# VME_buffers_data.net
KiCad netlist of a schematic drawn in Altium Designer
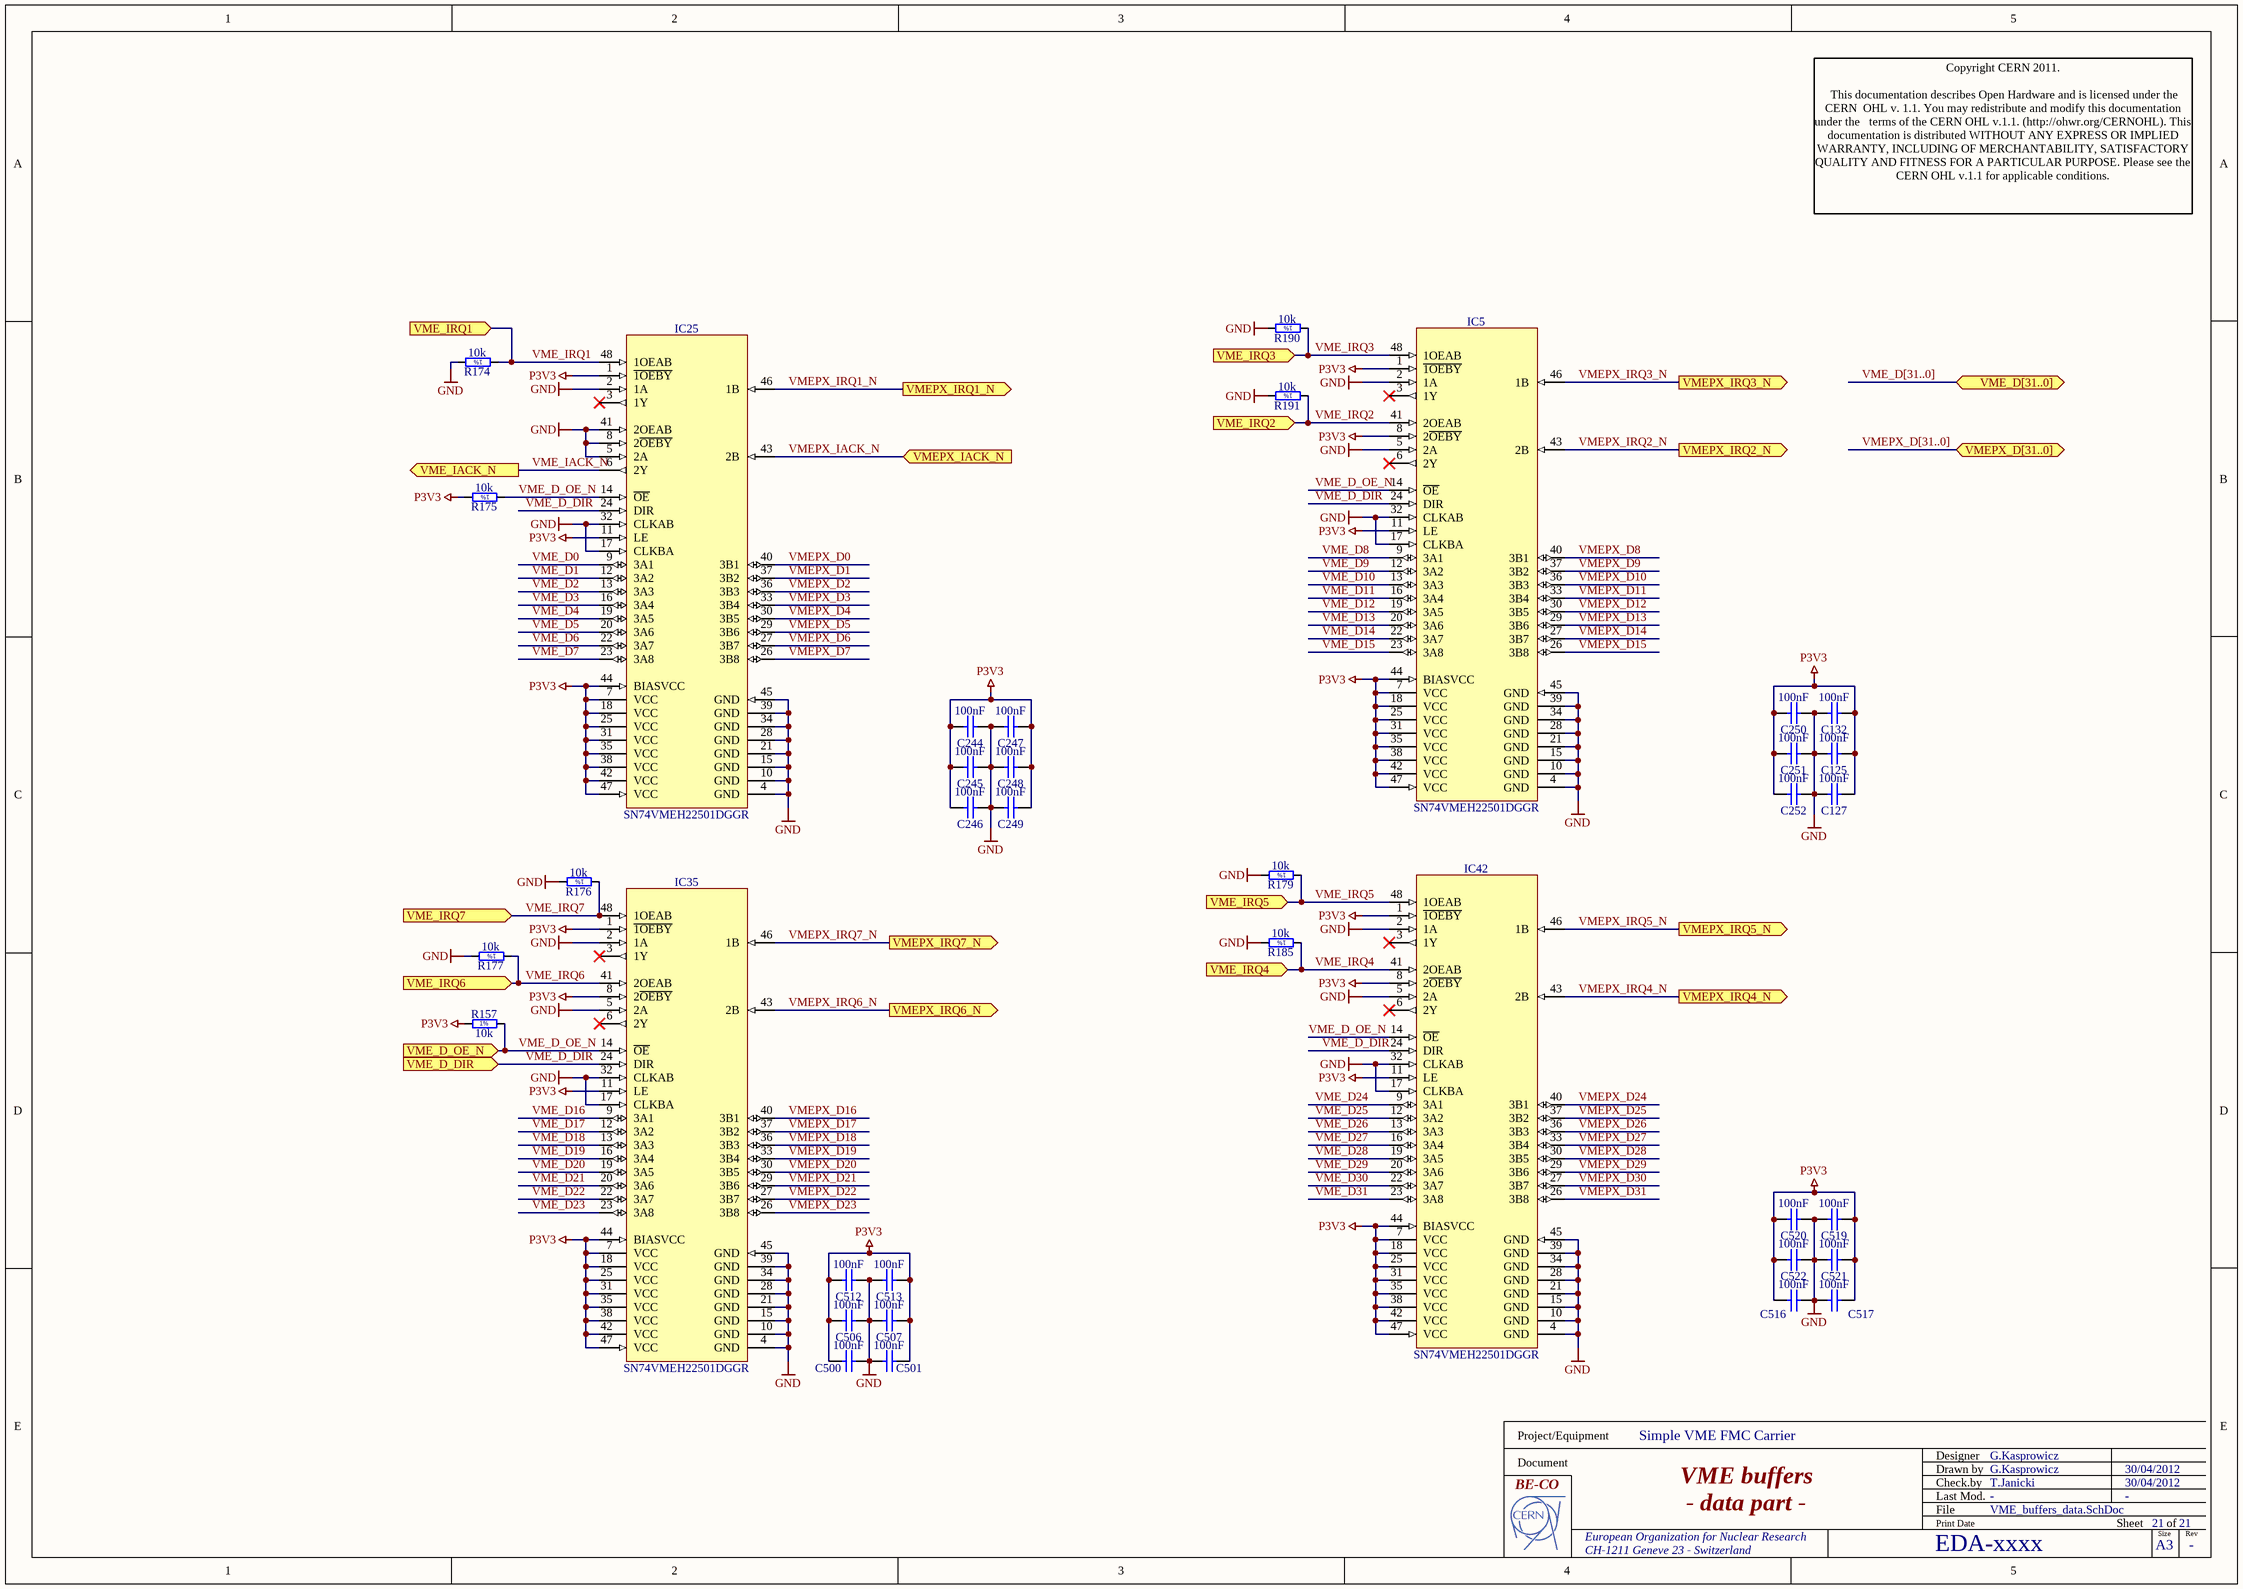
[diagram p0: VME_buffers_data.SchDoc]

(export (version "E")
  (design (tool "Eeschema 10.0.6"))
  (components
    (comp (ref "C125")
      (value "100nF")
      (footprint "CAPC1005X55N")
      (description "Non-polarised capacitor")
      (fields
        (field (name "PART NUMBER") "CC0402_100NF_16V_10%_X7R")
        (field (name "VOLTAGE") "16V")
        (field (name "AUTHOR") "CERN DEM JLC")
      )
      (libsource (lib "Capacitors") (part "Capacitor - non polarized"))
    )
    (comp (ref "C127")
      (value "100nF")
      (footprint "CAPC1005X55N")
      (description "Non-polarised capacitor")
      (fields
        (field (name "PART NUMBER") "CC0402_100NF_16V_10%_X7R")
        (field (name "VOLTAGE") "16V")
        (field (name "AUTHOR") "CERN DEM JLC")
      )
      (libsource (lib "Capacitors") (part "Capacitor - non polarized"))
    )
    (comp (ref "C132")
      (value "100nF")
      (footprint "CAPC1005X55N")
      (description "Non-polarised capacitor")
      (fields
        (field (name "PART NUMBER") "CC0402_100NF_16V_10%_X7R")
        (field (name "VOLTAGE") "16V")
        (field (name "AUTHOR") "CERN DEM JLC")
      )
      (libsource (lib "Capacitors") (part "Capacitor - non polarized"))
    )
    (comp (ref "C244")
      (value "100nF")
      (footprint "CAPC1005X55N")
      (description "Non-polarised capacitor")
      (fields
        (field (name "PART NUMBER") "CC0402_100NF_16V_10%_X7R")
        (field (name "VOLTAGE") "16V")
        (field (name "AUTHOR") "CERN DEM JLC")
      )
      (libsource (lib "Capacitors") (part "Capacitor - non polarized"))
    )
    (comp (ref "C245")
      (value "100nF")
      (footprint "CAPC1005X55N")
      (description "Non-polarised capacitor")
      (fields
        (field (name "PART NUMBER") "CC0402_100NF_16V_10%_X7R")
        (field (name "VOLTAGE") "16V")
        (field (name "AUTHOR") "CERN DEM JLC")
      )
      (libsource (lib "Capacitors") (part "Capacitor - non polarized"))
    )
    (comp (ref "C246")
      (value "100nF")
      (footprint "CAPC1005X55N")
      (description "Non-polarised capacitor")
      (fields
        (field (name "PART NUMBER") "CC0402_100NF_16V_10%_X7R")
        (field (name "VOLTAGE") "16V")
        (field (name "AUTHOR") "CERN DEM JLC")
      )
      (libsource (lib "Capacitors") (part "Capacitor - non polarized"))
    )
    (comp (ref "C247")
      (value "100nF")
      (footprint "CAPC1005X55N")
      (description "Non-polarised capacitor")
      (fields
        (field (name "PART NUMBER") "CC0402_100NF_16V_10%_X7R")
        (field (name "VOLTAGE") "16V")
        (field (name "AUTHOR") "CERN DEM JLC")
      )
      (libsource (lib "Capacitors") (part "Capacitor - non polarized"))
    )
    (comp (ref "C248")
      (value "100nF")
      (footprint "CAPC1005X55N")
      (description "Non-polarised capacitor")
      (fields
        (field (name "PART NUMBER") "CC0402_100NF_16V_10%_X7R")
        (field (name "VOLTAGE") "16V")
        (field (name "AUTHOR") "CERN DEM JLC")
      )
      (libsource (lib "Capacitors") (part "Capacitor - non polarized"))
    )
    (comp (ref "C249")
      (value "100nF")
      (footprint "CAPC1005X55N")
      (description "Non-polarised capacitor")
      (fields
        (field (name "PART NUMBER") "CC0402_100NF_16V_10%_X7R")
        (field (name "VOLTAGE") "16V")
        (field (name "AUTHOR") "CERN DEM JLC")
      )
      (libsource (lib "Capacitors") (part "Capacitor - non polarized"))
    )
    (comp (ref "C250")
      (value "100nF")
      (footprint "CAPC1005X55N")
      (description "Non-polarised capacitor")
      (fields
        (field (name "PART NUMBER") "CC0402_100NF_16V_10%_X7R")
        (field (name "VOLTAGE") "16V")
        (field (name "AUTHOR") "CERN DEM JLC")
      )
      (libsource (lib "Capacitors") (part "Capacitor - non polarized"))
    )
    (comp (ref "C251")
      (value "100nF")
      (footprint "CAPC1005X55N")
      (description "Non-polarised capacitor")
      (fields
        (field (name "PART NUMBER") "CC0402_100NF_16V_10%_X7R")
        (field (name "VOLTAGE") "16V")
        (field (name "AUTHOR") "CERN DEM JLC")
      )
      (libsource (lib "Capacitors") (part "Capacitor - non polarized"))
    )
    (comp (ref "C252")
      (value "100nF")
      (footprint "CAPC1005X55N")
      (description "Non-polarised capacitor")
      (fields
        (field (name "PART NUMBER") "CC0402_100NF_16V_10%_X7R")
        (field (name "VOLTAGE") "16V")
        (field (name "AUTHOR") "CERN DEM JLC")
      )
      (libsource (lib "Capacitors") (part "Capacitor - non polarized"))
    )
    (comp (ref "C500")
      (value "100nF")
      (footprint "CAPC1005X55N")
      (description "Non-polarised capacitor")
      (fields
        (field (name "PART NUMBER") "CC0402_100NF_16V_10%_X7R")
        (field (name "VOLTAGE") "16V")
        (field (name "AUTHOR") "CERN DEM JLC")
      )
      (libsource (lib "Capacitors") (part "Capacitor - non polarized"))
    )
    (comp (ref "C501")
      (value "100nF")
      (footprint "CAPC1005X55N")
      (description "Non-polarised capacitor")
      (fields
        (field (name "PART NUMBER") "CC0402_100NF_16V_10%_X7R")
        (field (name "VOLTAGE") "16V")
        (field (name "AUTHOR") "CERN DEM JLC")
      )
      (libsource (lib "Capacitors") (part "Capacitor - non polarized"))
    )
    (comp (ref "C506")
      (value "100nF")
      (footprint "CAPC1005X55N")
      (description "Non-polarised capacitor")
      (fields
        (field (name "PART NUMBER") "CC0402_100NF_16V_10%_X7R")
        (field (name "VOLTAGE") "16V")
        (field (name "AUTHOR") "CERN DEM JLC")
      )
      (libsource (lib "Capacitors") (part "Capacitor - non polarized"))
    )
    (comp (ref "C507")
      (value "100nF")
      (footprint "CAPC1005X55N")
      (description "Non-polarised capacitor")
      (fields
        (field (name "PART NUMBER") "CC0402_100NF_16V_10%_X7R")
        (field (name "VOLTAGE") "16V")
        (field (name "AUTHOR") "CERN DEM JLC")
      )
      (libsource (lib "Capacitors") (part "Capacitor - non polarized"))
    )
    (comp (ref "C512")
      (value "100nF")
      (footprint "CAPC1005X55N")
      (description "Non-polarised capacitor")
      (fields
        (field (name "PART NUMBER") "CC0402_100NF_16V_10%_X7R")
        (field (name "VOLTAGE") "16V")
        (field (name "AUTHOR") "CERN DEM JLC")
      )
      (libsource (lib "Capacitors") (part "Capacitor - non polarized"))
    )
    (comp (ref "C513")
      (value "100nF")
      (footprint "CAPC1005X55N")
      (description "Non-polarised capacitor")
      (fields
        (field (name "PART NUMBER") "CC0402_100NF_16V_10%_X7R")
        (field (name "VOLTAGE") "16V")
        (field (name "AUTHOR") "CERN DEM JLC")
      )
      (libsource (lib "Capacitors") (part "Capacitor - non polarized"))
    )
    (comp (ref "C516")
      (value "100nF")
      (footprint "CAPC1005X55N")
      (description "Non-polarised capacitor")
      (fields
        (field (name "PART NUMBER") "CC0402_100NF_16V_10%_X7R")
        (field (name "VOLTAGE") "16V")
        (field (name "AUTHOR") "CERN DEM JLC")
      )
      (libsource (lib "Capacitors") (part "Capacitor - non polarized"))
    )
    (comp (ref "C517")
      (value "100nF")
      (footprint "CAPC1005X55N")
      (description "Non-polarised capacitor")
      (fields
        (field (name "PART NUMBER") "CC0402_100NF_16V_10%_X7R")
        (field (name "VOLTAGE") "16V")
        (field (name "AUTHOR") "CERN DEM JLC")
      )
      (libsource (lib "Capacitors") (part "Capacitor - non polarized"))
    )
    (comp (ref "C519")
      (value "100nF")
      (footprint "CAPC1005X55N")
      (description "Non-polarised capacitor")
      (fields
        (field (name "PART NUMBER") "CC0402_100NF_16V_10%_X7R")
        (field (name "VOLTAGE") "16V")
        (field (name "AUTHOR") "CERN DEM JLC")
      )
      (libsource (lib "Capacitors") (part "Capacitor - non polarized"))
    )
    (comp (ref "C520")
      (value "100nF")
      (footprint "CAPC1005X55N")
      (description "Non-polarised capacitor")
      (fields
        (field (name "PART NUMBER") "CC0402_100NF_16V_10%_X7R")
        (field (name "VOLTAGE") "16V")
        (field (name "AUTHOR") "CERN DEM JLC")
      )
      (libsource (lib "Capacitors") (part "Capacitor - non polarized"))
    )
    (comp (ref "C521")
      (value "100nF")
      (footprint "CAPC1005X55N")
      (description "Non-polarised capacitor")
      (fields
        (field (name "PART NUMBER") "CC0402_100NF_16V_10%_X7R")
        (field (name "VOLTAGE") "16V")
        (field (name "AUTHOR") "CERN DEM JLC")
      )
      (libsource (lib "Capacitors") (part "Capacitor - non polarized"))
    )
    (comp (ref "C522")
      (value "100nF")
      (footprint "CAPC1005X55N")
      (description "Non-polarised capacitor")
      (fields
        (field (name "PART NUMBER") "CC0402_100NF_16V_10%_X7R")
        (field (name "VOLTAGE") "16V")
        (field (name "AUTHOR") "CERN DEM JLC")
      )
      (libsource (lib "Capacitors") (part "Capacitor - non polarized"))
    )
    (comp (ref "IC5")
      (value "SN74VMEH22501DGGR")
      (footprint "SOP50P810X120-48N")
      (description "8-Bit Universal Bus Transceiver and Two 1-Bit Bus Transceivers with 3-State Outputs")
      (fields (field (name "MANUFACTURER") "TEXAS INSTRUMENTS") (field (name "AUTHOR") "CERN DEM JLC"))
      (libsource (lib "ICs And Semiconductors") (part "74VMEH22501"))
    )
    (comp (ref "IC25")
      (value "SN74VMEH22501DGGR")
      (footprint "SOP50P810X120-48N")
      (description "8-Bit Universal Bus Transceiver and Two 1-Bit Bus Transceivers with 3-State Outputs")
      (fields (field (name "MANUFACTURER") "TEXAS INSTRUMENTS") (field (name "AUTHOR") "CERN DEM JLC"))
      (libsource (lib "ICs And Semiconductors") (part "74VMEH22501"))
    )
    (comp (ref "IC35")
      (value "SN74VMEH22501DGGR")
      (footprint "SOP50P810X120-48N")
      (description "8-Bit Universal Bus Transceiver and Two 1-Bit Bus Transceivers with 3-State Outputs")
      (fields (field (name "MANUFACTURER") "TEXAS INSTRUMENTS") (field (name "AUTHOR") "CERN DEM JLC"))
      (libsource (lib "ICs And Semiconductors") (part "74VMEH22501"))
    )
    (comp (ref "IC42")
      (value "SN74VMEH22501DGGR")
      (footprint "SOP50P810X120-48N")
      (description "8-Bit Universal Bus Transceiver and Two 1-Bit Bus Transceivers with 3-State Outputs")
      (fields (field (name "MANUFACTURER") "TEXAS INSTRUMENTS") (field (name "AUTHOR") "CERN DEM JLC"))
      (libsource (lib "ICs And Semiconductors") (part "74VMEH22501"))
    )
    (comp (ref "R157")
      (value "10k")
      (footprint "RESC1608X55N")
      (description "Resistor - 1%")
      (fields
        (field (name "PART NUMBER") "R0603_10K_1%_0.1W_100PPM")
        (field (name "POWER") "0.1W")
        (field (name "AUTHOR") "CERN DEM JLC")
      )
      (libsource (lib "Resistors") (part "Resistor - 1%"))
    )
    (comp (ref "R174")
      (value "10k")
      (footprint "RESC1608X55N")
      (description "Resistor - 1%")
      (fields
        (field (name "PART NUMBER") "R0603_10K_1%_0.1W_100PPM")
        (field (name "POWER") "0.1W")
        (field (name "AUTHOR") "CERN DEM JLC")
      )
      (libsource (lib "Resistors") (part "Resistor - 1%"))
    )
    (comp (ref "R175")
      (value "10k")
      (footprint "RESC1608X55N")
      (description "Resistor - 1%")
      (fields
        (field (name "PART NUMBER") "R0603_10K_1%_0.1W_100PPM")
        (field (name "POWER") "0.1W")
        (field (name "AUTHOR") "CERN DEM JLC")
      )
      (libsource (lib "Resistors") (part "Resistor - 1%"))
    )
    (comp (ref "R176")
      (value "10k")
      (footprint "RESC1608X55N")
      (description "Resistor - 1%")
      (fields
        (field (name "PART NUMBER") "R0603_10K_1%_0.1W_100PPM")
        (field (name "POWER") "0.1W")
        (field (name "AUTHOR") "CERN DEM JLC")
      )
      (libsource (lib "Resistors") (part "Resistor - 1%"))
    )
    (comp (ref "R177")
      (value "10k")
      (footprint "RESC1608X55N")
      (description "Resistor - 1%")
      (fields
        (field (name "PART NUMBER") "R0603_10K_1%_0.1W_100PPM")
        (field (name "POWER") "0.1W")
        (field (name "AUTHOR") "CERN DEM JLC")
      )
      (libsource (lib "Resistors") (part "Resistor - 1%"))
    )
    (comp (ref "R179")
      (value "10k")
      (footprint "RESC1608X55N")
      (description "Resistor - 1%")
      (fields
        (field (name "PART NUMBER") "R0603_10K_1%_0.1W_100PPM")
        (field (name "POWER") "0.1W")
        (field (name "AUTHOR") "CERN DEM JLC")
      )
      (libsource (lib "Resistors") (part "Resistor - 1%"))
    )
    (comp (ref "R185")
      (value "10k")
      (footprint "RESC1608X55N")
      (description "Resistor - 1%")
      (fields
        (field (name "PART NUMBER") "R0603_10K_1%_0.1W_100PPM")
        (field (name "POWER") "0.1W")
        (field (name "AUTHOR") "CERN DEM JLC")
      )
      (libsource (lib "Resistors") (part "Resistor - 1%"))
    )
    (comp (ref "R190")
      (value "10k")
      (footprint "RESC1608X55N")
      (description "Resistor - 1%")
      (fields
        (field (name "PART NUMBER") "R0603_10K_1%_0.1W_100PPM")
        (field (name "POWER") "0.1W")
        (field (name "AUTHOR") "CERN DEM JLC")
      )
      (libsource (lib "Resistors") (part "Resistor - 1%"))
    )
    (comp (ref "R191")
      (value "10k")
      (footprint "RESC1608X55N")
      (description "Resistor - 1%")
      (fields
        (field (name "PART NUMBER") "R0603_10K_1%_0.1W_100PPM")
        (field (name "POWER") "0.1W")
        (field (name "AUTHOR") "CERN DEM JLC")
      )
      (libsource (lib "Resistors") (part "Resistor - 1%"))
    )
  )
  (nets
    (net (code "1") (name "/VMEPX_D0") (class "Default")
      (node (ref "IC25") (pin "40") (pinfunction "3B1_40") (pintype "bidirectional"))
    )
    (net (code "2") (name "/VMEPX_D1") (class "Default")
      (node (ref "IC25") (pin "37") (pinfunction "3B2_37") (pintype "bidirectional"))
    )
    (net (code "3") (name "/VMEPX_D2") (class "Default")
      (node (ref "IC25") (pin "36") (pinfunction "3B3_36") (pintype "bidirectional"))
    )
    (net (code "4") (name "/VMEPX_D3") (class "Default")
      (node (ref "IC25") (pin "33") (pinfunction "3B4_33") (pintype "bidirectional"))
    )
    (net (code "5") (name "/VMEPX_D4") (class "Default")
      (node (ref "IC25") (pin "30") (pinfunction "3B5_30") (pintype "bidirectional"))
    )
    (net (code "6") (name "/VMEPX_D5") (class "Default")
      (node (ref "IC25") (pin "29") (pinfunction "3B6_29") (pintype "bidirectional"))
    )
    (net (code "7") (name "/VMEPX_D6") (class "Default")
      (node (ref "IC25") (pin "27") (pinfunction "3B7_27") (pintype "bidirectional"))
    )
    (net (code "8") (name "/VMEPX_D7") (class "Default")
      (node (ref "IC25") (pin "26") (pinfunction "3B8_26") (pintype "bidirectional"))
    )
    (net (code "9") (name "/VMEPX_D8") (class "Default")
      (node (ref "IC5") (pin "40") (pinfunction "3B1_40") (pintype "bidirectional"))
    )
    (net (code "10") (name "/VMEPX_D9") (class "Default")
      (node (ref "IC5") (pin "37") (pinfunction "3B2_37") (pintype "bidirectional"))
    )
    (net (code "11") (name "/VMEPX_D10") (class "Default")
      (node (ref "IC5") (pin "36") (pinfunction "3B3_36") (pintype "bidirectional"))
    )
    (net (code "12") (name "/VMEPX_D11") (class "Default")
      (node (ref "IC5") (pin "33") (pinfunction "3B4_33") (pintype "bidirectional"))
    )
    (net (code "13") (name "/VMEPX_D12") (class "Default")
      (node (ref "IC5") (pin "30") (pinfunction "3B5_30") (pintype "bidirectional"))
    )
    (net (code "14") (name "/VMEPX_D13") (class "Default")
      (node (ref "IC5") (pin "29") (pinfunction "3B6_29") (pintype "bidirectional"))
    )
    (net (code "15") (name "/VMEPX_D14") (class "Default")
      (node (ref "IC5") (pin "27") (pinfunction "3B7_27") (pintype "bidirectional"))
    )
    (net (code "16") (name "/VMEPX_D15") (class "Default")
      (node (ref "IC5") (pin "26") (pinfunction "3B8_26") (pintype "bidirectional"))
    )
    (net (code "17") (name "/VMEPX_D16") (class "Default")
      (node (ref "IC35") (pin "40") (pinfunction "3B1_40") (pintype "bidirectional"))
    )
    (net (code "18") (name "/VMEPX_D17") (class "Default")
      (node (ref "IC35") (pin "37") (pinfunction "3B2_37") (pintype "bidirectional"))
    )
    (net (code "19") (name "/VMEPX_D18") (class "Default")
      (node (ref "IC35") (pin "36") (pinfunction "3B3_36") (pintype "bidirectional"))
    )
    (net (code "20") (name "/VMEPX_D19") (class "Default")
      (node (ref "IC35") (pin "33") (pinfunction "3B4_33") (pintype "bidirectional"))
    )
    (net (code "21") (name "/VMEPX_D20") (class "Default")
      (node (ref "IC35") (pin "30") (pinfunction "3B5_30") (pintype "bidirectional"))
    )
    (net (code "22") (name "/VMEPX_D21") (class "Default")
      (node (ref "IC35") (pin "29") (pinfunction "3B6_29") (pintype "bidirectional"))
    )
    (net (code "23") (name "/VMEPX_D22") (class "Default")
      (node (ref "IC35") (pin "27") (pinfunction "3B7_27") (pintype "bidirectional"))
    )
    (net (code "24") (name "/VMEPX_D23") (class "Default")
      (node (ref "IC35") (pin "26") (pinfunction "3B8_26") (pintype "bidirectional"))
    )
    (net (code "25") (name "/VMEPX_D24") (class "Default")
      (node (ref "IC42") (pin "40") (pinfunction "3B1_40") (pintype "bidirectional"))
    )
    (net (code "26") (name "/VMEPX_D25") (class "Default")
      (node (ref "IC42") (pin "37") (pinfunction "3B2_37") (pintype "bidirectional"))
    )
    (net (code "27") (name "/VMEPX_D26") (class "Default")
      (node (ref "IC42") (pin "36") (pinfunction "3B3_36") (pintype "bidirectional"))
    )
    (net (code "28") (name "/VMEPX_D27") (class "Default")
      (node (ref "IC42") (pin "33") (pinfunction "3B4_33") (pintype "bidirectional"))
    )
    (net (code "29") (name "/VMEPX_D28") (class "Default")
      (node (ref "IC42") (pin "30") (pinfunction "3B5_30") (pintype "bidirectional"))
    )
    (net (code "30") (name "/VMEPX_D29") (class "Default")
      (node (ref "IC42") (pin "29") (pinfunction "3B6_29") (pintype "bidirectional"))
    )
    (net (code "31") (name "/VMEPX_D30") (class "Default")
      (node (ref "IC42") (pin "27") (pinfunction "3B7_27") (pintype "bidirectional"))
    )
    (net (code "32") (name "/VMEPX_D31") (class "Default")
      (node (ref "IC42") (pin "26") (pinfunction "3B8_26") (pintype "bidirectional"))
    )
    (net (code "34") (name "/VMEPX_IACK_N") (class "Default")
      (node (ref "IC25") (pin "43") (pinfunction "2B_43") (pintype "input"))
    )
    (net (code "35") (name "/VMEPX_IRQ1_N") (class "Default")
      (node (ref "IC25") (pin "46") (pinfunction "1B_46") (pintype "input"))
    )
    (net (code "36") (name "/VMEPX_IRQ2_N") (class "Default")
      (node (ref "IC5") (pin "43") (pinfunction "2B_43") (pintype "input"))
    )
    (net (code "37") (name "/VMEPX_IRQ3_N") (class "Default")
      (node (ref "IC5") (pin "46") (pinfunction "1B_46") (pintype "input"))
    )
    (net (code "38") (name "/VMEPX_IRQ4_N") (class "Default")
      (node (ref "IC42") (pin "43") (pinfunction "2B_43") (pintype "input"))
    )
    (net (code "39") (name "/VMEPX_IRQ5_N") (class "Default")
      (node (ref "IC42") (pin "46") (pinfunction "1B_46") (pintype "input"))
    )
    (net (code "40") (name "/VMEPX_IRQ6_N") (class "Default")
      (node (ref "IC35") (pin "43") (pinfunction "2B_43") (pintype "input"))
    )
    (net (code "41") (name "/VMEPX_IRQ7_N") (class "Default")
      (node (ref "IC35") (pin "46") (pinfunction "1B_46") (pintype "input"))
    )
    (net (code "42") (name "/VME_D0") (class "Default")
      (node (ref "IC25") (pin "9") (pinfunction "3A1_9") (pintype "bidirectional"))
    )
    (net (code "43") (name "/VME_D1") (class "Default")
      (node (ref "IC25") (pin "12") (pinfunction "3A2_12") (pintype "bidirectional"))
    )
    (net (code "44") (name "/VME_D2") (class "Default")
      (node (ref "IC25") (pin "13") (pinfunction "3A3_13") (pintype "bidirectional"))
    )
    (net (code "45") (name "/VME_D3") (class "Default")
      (node (ref "IC25") (pin "16") (pinfunction "3A4_16") (pintype "bidirectional"))
    )
    (net (code "46") (name "/VME_D4") (class "Default")
      (node (ref "IC25") (pin "19") (pinfunction "3A5_19") (pintype "bidirectional"))
    )
    (net (code "47") (name "/VME_D5") (class "Default")
      (node (ref "IC25") (pin "20") (pinfunction "3A6_20") (pintype "bidirectional"))
    )
    (net (code "48") (name "/VME_D6") (class "Default")
      (node (ref "IC25") (pin "22") (pinfunction "3A7_22") (pintype "bidirectional"))
    )
    (net (code "49") (name "/VME_D7") (class "Default")
      (node (ref "IC25") (pin "23") (pinfunction "3A8_23") (pintype "bidirectional"))
    )
    (net (code "50") (name "/VME_D8") (class "Default")
      (node (ref "IC5") (pin "9") (pinfunction "3A1_9") (pintype "bidirectional"))
    )
    (net (code "51") (name "/VME_D9") (class "Default")
      (node (ref "IC5") (pin "12") (pinfunction "3A2_12") (pintype "bidirectional"))
    )
    (net (code "52") (name "/VME_D10") (class "Default")
      (node (ref "IC5") (pin "13") (pinfunction "3A3_13") (pintype "bidirectional"))
    )
    (net (code "53") (name "/VME_D11") (class "Default")
      (node (ref "IC5") (pin "16") (pinfunction "3A4_16") (pintype "bidirectional"))
    )
    (net (code "54") (name "/VME_D12") (class "Default")
      (node (ref "IC5") (pin "19") (pinfunction "3A5_19") (pintype "bidirectional"))
    )
    (net (code "55") (name "/VME_D13") (class "Default")
      (node (ref "IC5") (pin "20") (pinfunction "3A6_20") (pintype "bidirectional"))
    )
    (net (code "56") (name "/VME_D14") (class "Default")
      (node (ref "IC5") (pin "22") (pinfunction "3A7_22") (pintype "bidirectional"))
    )
    (net (code "57") (name "/VME_D15") (class "Default")
      (node (ref "IC5") (pin "23") (pinfunction "3A8_23") (pintype "bidirectional"))
    )
    (net (code "58") (name "/VME_D16") (class "Default")
      (node (ref "IC35") (pin "9") (pinfunction "3A1_9") (pintype "bidirectional"))
    )
    (net (code "59") (name "/VME_D17") (class "Default")
      (node (ref "IC35") (pin "12") (pinfunction "3A2_12") (pintype "bidirectional"))
    )
    (net (code "60") (name "/VME_D18") (class "Default")
      (node (ref "IC35") (pin "13") (pinfunction "3A3_13") (pintype "bidirectional"))
    )
    (net (code "61") (name "/VME_D19") (class "Default")
      (node (ref "IC35") (pin "16") (pinfunction "3A4_16") (pintype "bidirectional"))
    )
    (net (code "62") (name "/VME_D20") (class "Default")
      (node (ref "IC35") (pin "19") (pinfunction "3A5_19") (pintype "bidirectional"))
    )
    (net (code "63") (name "/VME_D21") (class "Default")
      (node (ref "IC35") (pin "20") (pinfunction "3A6_20") (pintype "bidirectional"))
    )
    (net (code "64") (name "/VME_D22") (class "Default")
      (node (ref "IC35") (pin "22") (pinfunction "3A7_22") (pintype "bidirectional"))
    )
    (net (code "65") (name "/VME_D23") (class "Default")
      (node (ref "IC35") (pin "23") (pinfunction "3A8_23") (pintype "bidirectional"))
    )
    (net (code "66") (name "/VME_D24") (class "Default")
      (node (ref "IC42") (pin "9") (pinfunction "3A1_9") (pintype "bidirectional"))
    )
    (net (code "67") (name "/VME_D25") (class "Default")
      (node (ref "IC42") (pin "12") (pinfunction "3A2_12") (pintype "bidirectional"))
    )
    (net (code "68") (name "/VME_D26") (class "Default")
      (node (ref "IC42") (pin "13") (pinfunction "3A3_13") (pintype "bidirectional"))
    )
    (net (code "69") (name "/VME_D27") (class "Default")
      (node (ref "IC42") (pin "16") (pinfunction "3A4_16") (pintype "bidirectional"))
    )
    (net (code "70") (name "/VME_D28") (class "Default")
      (node (ref "IC42") (pin "19") (pinfunction "3A5_19") (pintype "bidirectional"))
    )
    (net (code "71") (name "/VME_D29") (class "Default")
      (node (ref "IC42") (pin "20") (pinfunction "3A6_20") (pintype "bidirectional"))
    )
    (net (code "72") (name "/VME_D30") (class "Default")
      (node (ref "IC42") (pin "22") (pinfunction "3A7_22") (pintype "bidirectional"))
    )
    (net (code "73") (name "/VME_D31") (class "Default")
      (node (ref "IC42") (pin "23") (pinfunction "3A8_23") (pintype "bidirectional"))
    )
    (net (code "75") (name "/VME_D_DIR") (class "Default")
      (node (ref "IC25") (pin "24") (pinfunction "DIR_24") (pintype "input"))
      (node (ref "IC35") (pin "24") (pinfunction "DIR_24") (pintype "input"))
      (node (ref "IC42") (pin "24") (pinfunction "DIR_24") (pintype "input"))
      (node (ref "IC5") (pin "24") (pinfunction "DIR_24") (pintype "input"))
    )
    (net (code "76") (name "/VME_D_OE_N") (class "Default")
      (node (ref "IC25") (pin "14") (pinfunction "~{OE}_14") (pintype "input"))
      (node (ref "IC35") (pin "14") (pinfunction "~{OE}_14") (pintype "input"))
      (node (ref "IC42") (pin "14") (pinfunction "~{OE}_14") (pintype "input"))
      (node (ref "IC5") (pin "14") (pinfunction "~{OE}_14") (pintype "input"))
      (node (ref "R157") (pin "2") (pinfunction "2_2") (pintype "passive"))
      (node (ref "R175") (pin "1") (pinfunction "1_1") (pintype "passive"))
    )
    (net (code "77") (name "/VME_IACK_N") (class "Default")
      (node (ref "IC25") (pin "6") (pinfunction "2Y_6") (pintype "output"))
    )
    (net (code "78") (name "/VME_IRQ1") (class "Default")
      (node (ref "IC25") (pin "48") (pinfunction "1OEAB_48") (pintype "input"))
      (node (ref "R174") (pin "1") (pinfunction "1_1") (pintype "passive"))
    )
    (net (code "79") (name "/VME_IRQ2") (class "Default")
      (node (ref "IC5") (pin "41") (pinfunction "2OEAB_41") (pintype "input"))
      (node (ref "R191") (pin "1") (pinfunction "1_1") (pintype "passive"))
    )
    (net (code "80") (name "/VME_IRQ3") (class "Default")
      (node (ref "IC5") (pin "48") (pinfunction "1OEAB_48") (pintype "input"))
      (node (ref "R190") (pin "1") (pinfunction "1_1") (pintype "passive"))
    )
    (net (code "81") (name "/VME_IRQ4") (class "Default")
      (node (ref "IC42") (pin "41") (pinfunction "2OEAB_41") (pintype "input"))
      (node (ref "R185") (pin "1") (pinfunction "1_1") (pintype "passive"))
    )
    (net (code "82") (name "/VME_IRQ5") (class "Default")
      (node (ref "IC42") (pin "48") (pinfunction "1OEAB_48") (pintype "input"))
      (node (ref "R179") (pin "1") (pinfunction "1_1") (pintype "passive"))
    )
    (net (code "83") (name "/VME_IRQ6") (class "Default")
      (node (ref "IC35") (pin "41") (pinfunction "2OEAB_41") (pintype "input"))
      (node (ref "R177") (pin "1") (pinfunction "1_1") (pintype "passive"))
    )
    (net (code "84") (name "/VME_IRQ7") (class "Default")
      (node (ref "IC35") (pin "48") (pinfunction "1OEAB_48") (pintype "input"))
      (node (ref "R176") (pin "1") (pinfunction "1_1") (pintype "passive"))
    )
    (net (code "85") (name "GND") (class "Default")
      (node (ref "C125") (pin "2") (pinfunction "2_2") (pintype "passive"))
      (node (ref "C127") (pin "2") (pinfunction "2_2") (pintype "passive"))
      (node (ref "C132") (pin "2") (pinfunction "2_2") (pintype "passive"))
      (node (ref "C244") (pin "1") (pinfunction "1_1") (pintype "passive"))
      (node (ref "C245") (pin "1") (pinfunction "1_1") (pintype "passive"))
      (node (ref "C246") (pin "1") (pinfunction "1_1") (pintype "passive"))
      (node (ref "C247") (pin "2") (pinfunction "2_2") (pintype "passive"))
      (node (ref "C248") (pin "2") (pinfunction "2_2") (pintype "passive"))
      (node (ref "C249") (pin "2") (pinfunction "2_2") (pintype "passive"))
      (node (ref "C250") (pin "1") (pinfunction "1_1") (pintype "passive"))
      (node (ref "C251") (pin "1") (pinfunction "1_1") (pintype "passive"))
      (node (ref "C252") (pin "1") (pinfunction "1_1") (pintype "passive"))
      (node (ref "C500") (pin "1") (pinfunction "1_1") (pintype "passive"))
      (node (ref "C501") (pin "2") (pinfunction "2_2") (pintype "passive"))
      (node (ref "C506") (pin "1") (pinfunction "1_1") (pintype "passive"))
      (node (ref "C507") (pin "2") (pinfunction "2_2") (pintype "passive"))
      (node (ref "C512") (pin "1") (pinfunction "1_1") (pintype "passive"))
      (node (ref "C513") (pin "2") (pinfunction "2_2") (pintype "passive"))
      (node (ref "C516") (pin "1") (pinfunction "1_1") (pintype "passive"))
      (node (ref "C517") (pin "2") (pinfunction "2_2") (pintype "passive"))
      (node (ref "C519") (pin "2") (pinfunction "2_2") (pintype "passive"))
      (node (ref "C520") (pin "1") (pinfunction "1_1") (pintype "passive"))
      (node (ref "C521") (pin "2") (pinfunction "2_2") (pintype "passive"))
      (node (ref "C522") (pin "1") (pinfunction "1_1") (pintype "passive"))
      (node (ref "IC25") (pin "10") (pinfunction "GND_10") (pintype "power_in"))
      (node (ref "IC25") (pin "15") (pinfunction "GND_15") (pintype "power_in"))
      (node (ref "IC25") (pin "17") (pinfunction "CLKBA_17") (pintype "input"))
      (node (ref "IC25") (pin "2") (pinfunction "1A_2") (pintype "input"))
      (node (ref "IC25") (pin "21") (pinfunction "GND_21") (pintype "power_in"))
      (node (ref "IC25") (pin "28") (pinfunction "GND_28") (pintype "power_in"))
      (node (ref "IC25") (pin "32") (pinfunction "CLKAB_32") (pintype "input"))
      (node (ref "IC25") (pin "34") (pinfunction "GND_34") (pintype "power_in"))
      (node (ref "IC25") (pin "39") (pinfunction "GND_39") (pintype "power_in"))
      (node (ref "IC25") (pin "4") (pinfunction "GND_4") (pintype "power_in"))
      (node (ref "IC25") (pin "41") (pinfunction "2OEAB_41") (pintype "input"))
      (node (ref "IC25") (pin "45") (pinfunction "GND_45") (pintype "input"))
      (node (ref "IC25") (pin "5") (pinfunction "2A_5") (pintype "input"))
      (node (ref "IC25") (pin "8") (pinfunction "2~{OEBY}_8") (pintype "input"))
      (node (ref "IC35") (pin "10") (pinfunction "GND_10") (pintype "power_in"))
      (node (ref "IC35") (pin "15") (pinfunction "GND_15") (pintype "power_in"))
      (node (ref "IC35") (pin "17") (pinfunction "CLKBA_17") (pintype "input"))
      (node (ref "IC35") (pin "2") (pinfunction "1A_2") (pintype "input"))
      (node (ref "IC35") (pin "21") (pinfunction "GND_21") (pintype "power_in"))
      (node (ref "IC35") (pin "28") (pinfunction "GND_28") (pintype "power_in"))
      (node (ref "IC35") (pin "32") (pinfunction "CLKAB_32") (pintype "input"))
      (node (ref "IC35") (pin "34") (pinfunction "GND_34") (pintype "power_in"))
      (node (ref "IC35") (pin "39") (pinfunction "GND_39") (pintype "power_in"))
      (node (ref "IC35") (pin "4") (pinfunction "GND_4") (pintype "power_in"))
      (node (ref "IC35") (pin "45") (pinfunction "GND_45") (pintype "input"))
      (node (ref "IC35") (pin "5") (pinfunction "2A_5") (pintype "input"))
      (node (ref "IC42") (pin "10") (pinfunction "GND_10") (pintype "power_in"))
      (node (ref "IC42") (pin "15") (pinfunction "GND_15") (pintype "power_in"))
      (node (ref "IC42") (pin "17") (pinfunction "CLKBA_17") (pintype "input"))
      (node (ref "IC42") (pin "2") (pinfunction "1A_2") (pintype "input"))
      (node (ref "IC42") (pin "21") (pinfunction "GND_21") (pintype "power_in"))
      (node (ref "IC42") (pin "28") (pinfunction "GND_28") (pintype "power_in"))
      (node (ref "IC42") (pin "32") (pinfunction "CLKAB_32") (pintype "input"))
      (node (ref "IC42") (pin "34") (pinfunction "GND_34") (pintype "power_in"))
      (node (ref "IC42") (pin "39") (pinfunction "GND_39") (pintype "power_in"))
      (node (ref "IC42") (pin "4") (pinfunction "GND_4") (pintype "power_in"))
      (node (ref "IC42") (pin "45") (pinfunction "GND_45") (pintype "input"))
      (node (ref "IC42") (pin "5") (pinfunction "2A_5") (pintype "input"))
      (node (ref "IC5") (pin "10") (pinfunction "GND_10") (pintype "power_in"))
      (node (ref "IC5") (pin "15") (pinfunction "GND_15") (pintype "power_in"))
      (node (ref "IC5") (pin "17") (pinfunction "CLKBA_17") (pintype "input"))
      (node (ref "IC5") (pin "2") (pinfunction "1A_2") (pintype "input"))
      (node (ref "IC5") (pin "21") (pinfunction "GND_21") (pintype "power_in"))
      (node (ref "IC5") (pin "28") (pinfunction "GND_28") (pintype "power_in"))
      (node (ref "IC5") (pin "32") (pinfunction "CLKAB_32") (pintype "input"))
      (node (ref "IC5") (pin "34") (pinfunction "GND_34") (pintype "power_in"))
      (node (ref "IC5") (pin "39") (pinfunction "GND_39") (pintype "power_in"))
      (node (ref "IC5") (pin "4") (pinfunction "GND_4") (pintype "power_in"))
      (node (ref "IC5") (pin "45") (pinfunction "GND_45") (pintype "input"))
      (node (ref "IC5") (pin "5") (pinfunction "2A_5") (pintype "input"))
      (node (ref "R174") (pin "2") (pinfunction "2_2") (pintype "passive"))
      (node (ref "R176") (pin "2") (pinfunction "2_2") (pintype "passive"))
      (node (ref "R177") (pin "2") (pinfunction "2_2") (pintype "passive"))
      (node (ref "R179") (pin "2") (pinfunction "2_2") (pintype "passive"))
      (node (ref "R185") (pin "2") (pinfunction "2_2") (pintype "passive"))
      (node (ref "R190") (pin "2") (pinfunction "2_2") (pintype "passive"))
      (node (ref "R191") (pin "2") (pinfunction "2_2") (pintype "passive"))
    )
    (net (code "86") (name "P3V3") (class "Default")
      (node (ref "C125") (pin "1") (pinfunction "1_1") (pintype "passive"))
      (node (ref "C127") (pin "1") (pinfunction "1_1") (pintype "passive"))
      (node (ref "C132") (pin "1") (pinfunction "1_1") (pintype "passive"))
      (node (ref "C244") (pin "2") (pinfunction "2_2") (pintype "passive"))
      (node (ref "C245") (pin "2") (pinfunction "2_2") (pintype "passive"))
      (node (ref "C246") (pin "2") (pinfunction "2_2") (pintype "passive"))
      (node (ref "C247") (pin "1") (pinfunction "1_1") (pintype "passive"))
      (node (ref "C248") (pin "1") (pinfunction "1_1") (pintype "passive"))
      (node (ref "C249") (pin "1") (pinfunction "1_1") (pintype "passive"))
      (node (ref "C250") (pin "2") (pinfunction "2_2") (pintype "passive"))
      (node (ref "C251") (pin "2") (pinfunction "2_2") (pintype "passive"))
      (node (ref "C252") (pin "2") (pinfunction "2_2") (pintype "passive"))
      (node (ref "C500") (pin "2") (pinfunction "2_2") (pintype "passive"))
      (node (ref "C501") (pin "1") (pinfunction "1_1") (pintype "passive"))
      (node (ref "C506") (pin "2") (pinfunction "2_2") (pintype "passive"))
      (node (ref "C507") (pin "1") (pinfunction "1_1") (pintype "passive"))
      (node (ref "C512") (pin "2") (pinfunction "2_2") (pintype "passive"))
      (node (ref "C513") (pin "1") (pinfunction "1_1") (pintype "passive"))
      (node (ref "C516") (pin "2") (pinfunction "2_2") (pintype "passive"))
      (node (ref "C517") (pin "1") (pinfunction "1_1") (pintype "passive"))
      (node (ref "C519") (pin "1") (pinfunction "1_1") (pintype "passive"))
      (node (ref "C520") (pin "2") (pinfunction "2_2") (pintype "passive"))
      (node (ref "C521") (pin "1") (pinfunction "1_1") (pintype "passive"))
      (node (ref "C522") (pin "2") (pinfunction "2_2") (pintype "passive"))
      (node (ref "IC25") (pin "1") (pinfunction "~{1OEBY}_1") (pintype "input"))
      (node (ref "IC25") (pin "11") (pinfunction "LE_11") (pintype "input"))
      (node (ref "IC25") (pin "18") (pinfunction "VCC_18") (pintype "power_in"))
      (node (ref "IC25") (pin "25") (pinfunction "VCC_25") (pintype "power_in"))
      (node (ref "IC25") (pin "31") (pinfunction "VCC_31") (pintype "power_in"))
      (node (ref "IC25") (pin "35") (pinfunction "VCC_35") (pintype "power_in"))
      (node (ref "IC25") (pin "38") (pinfunction "VCC_38") (pintype "power_in"))
      (node (ref "IC25") (pin "42") (pinfunction "VCC_42") (pintype "power_in"))
      (node (ref "IC25") (pin "44") (pinfunction "BIASVCC_44") (pintype "input"))
      (node (ref "IC25") (pin "47") (pinfunction "VCC_47") (pintype "input"))
      (node (ref "IC25") (pin "7") (pinfunction "VCC_7") (pintype "power_in"))
      (node (ref "IC35") (pin "1") (pinfunction "~{1OEBY}_1") (pintype "input"))
      (node (ref "IC35") (pin "11") (pinfunction "LE_11") (pintype "input"))
      (node (ref "IC35") (pin "18") (pinfunction "VCC_18") (pintype "power_in"))
      (node (ref "IC35") (pin "25") (pinfunction "VCC_25") (pintype "power_in"))
      (node (ref "IC35") (pin "31") (pinfunction "VCC_31") (pintype "power_in"))
      (node (ref "IC35") (pin "35") (pinfunction "VCC_35") (pintype "power_in"))
      (node (ref "IC35") (pin "38") (pinfunction "VCC_38") (pintype "power_in"))
      (node (ref "IC35") (pin "42") (pinfunction "VCC_42") (pintype "power_in"))
      (node (ref "IC35") (pin "44") (pinfunction "BIASVCC_44") (pintype "input"))
      (node (ref "IC35") (pin "47") (pinfunction "VCC_47") (pintype "input"))
      (node (ref "IC35") (pin "7") (pinfunction "VCC_7") (pintype "power_in"))
      (node (ref "IC35") (pin "8") (pinfunction "2~{OEBY}_8") (pintype "input"))
      (node (ref "IC42") (pin "1") (pinfunction "~{1OEBY}_1") (pintype "input"))
      (node (ref "IC42") (pin "11") (pinfunction "LE_11") (pintype "input"))
      (node (ref "IC42") (pin "18") (pinfunction "VCC_18") (pintype "power_in"))
      (node (ref "IC42") (pin "25") (pinfunction "VCC_25") (pintype "power_in"))
      (node (ref "IC42") (pin "31") (pinfunction "VCC_31") (pintype "power_in"))
      (node (ref "IC42") (pin "35") (pinfunction "VCC_35") (pintype "power_in"))
      (node (ref "IC42") (pin "38") (pinfunction "VCC_38") (pintype "power_in"))
      (node (ref "IC42") (pin "42") (pinfunction "VCC_42") (pintype "power_in"))
      (node (ref "IC42") (pin "44") (pinfunction "BIASVCC_44") (pintype "input"))
      (node (ref "IC42") (pin "47") (pinfunction "VCC_47") (pintype "input"))
      (node (ref "IC42") (pin "7") (pinfunction "VCC_7") (pintype "power_in"))
      (node (ref "IC42") (pin "8") (pinfunction "2~{OEBY}_8") (pintype "input"))
      (node (ref "IC5") (pin "1") (pinfunction "~{1OEBY}_1") (pintype "input"))
      (node (ref "IC5") (pin "11") (pinfunction "LE_11") (pintype "input"))
      (node (ref "IC5") (pin "18") (pinfunction "VCC_18") (pintype "power_in"))
      (node (ref "IC5") (pin "25") (pinfunction "VCC_25") (pintype "power_in"))
      (node (ref "IC5") (pin "31") (pinfunction "VCC_31") (pintype "power_in"))
      (node (ref "IC5") (pin "35") (pinfunction "VCC_35") (pintype "power_in"))
      (node (ref "IC5") (pin "38") (pinfunction "VCC_38") (pintype "power_in"))
      (node (ref "IC5") (pin "42") (pinfunction "VCC_42") (pintype "power_in"))
      (node (ref "IC5") (pin "44") (pinfunction "BIASVCC_44") (pintype "input"))
      (node (ref "IC5") (pin "47") (pinfunction "VCC_47") (pintype "input"))
      (node (ref "IC5") (pin "7") (pinfunction "VCC_7") (pintype "power_in"))
      (node (ref "IC5") (pin "8") (pinfunction "2~{OEBY}_8") (pintype "input"))
      (node (ref "R157") (pin "1") (pinfunction "1_1") (pintype "passive"))
      (node (ref "R175") (pin "2") (pinfunction "2_2") (pintype "passive"))
    )
    (net (code "87") (name "unconnected-(IC5-1Y-Pad3)") (class "Default")
      (node (ref "IC5") (pin "3") (pinfunction "1Y_3") (pintype "output+no_connect"))
    )
    (net (code "88") (name "unconnected-(IC5-2Y-Pad6)") (class "Default")
      (node (ref "IC5") (pin "6") (pinfunction "2Y_6") (pintype "output+no_connect"))
    )
    (net (code "89") (name "unconnected-(IC25-1Y-Pad3)") (class "Default")
      (node (ref "IC25") (pin "3") (pinfunction "1Y_3") (pintype "output+no_connect"))
    )
    (net (code "90") (name "unconnected-(IC35-1Y-Pad3)") (class "Default")
      (node (ref "IC35") (pin "3") (pinfunction "1Y_3") (pintype "output+no_connect"))
    )
    (net (code "91") (name "unconnected-(IC35-2Y-Pad6)") (class "Default")
      (node (ref "IC35") (pin "6") (pinfunction "2Y_6") (pintype "output+no_connect"))
    )
    (net (code "92") (name "unconnected-(IC42-1Y-Pad3)") (class "Default")
      (node (ref "IC42") (pin "3") (pinfunction "1Y_3") (pintype "output+no_connect"))
    )
    (net (code "93") (name "unconnected-(IC42-2Y-Pad6)") (class "Default")
      (node (ref "IC42") (pin "6") (pinfunction "2Y_6") (pintype "output+no_connect"))
    )
  )
)
